# Microcontroller.net
KiCad netlist of a schematic drawn in Altium Designer
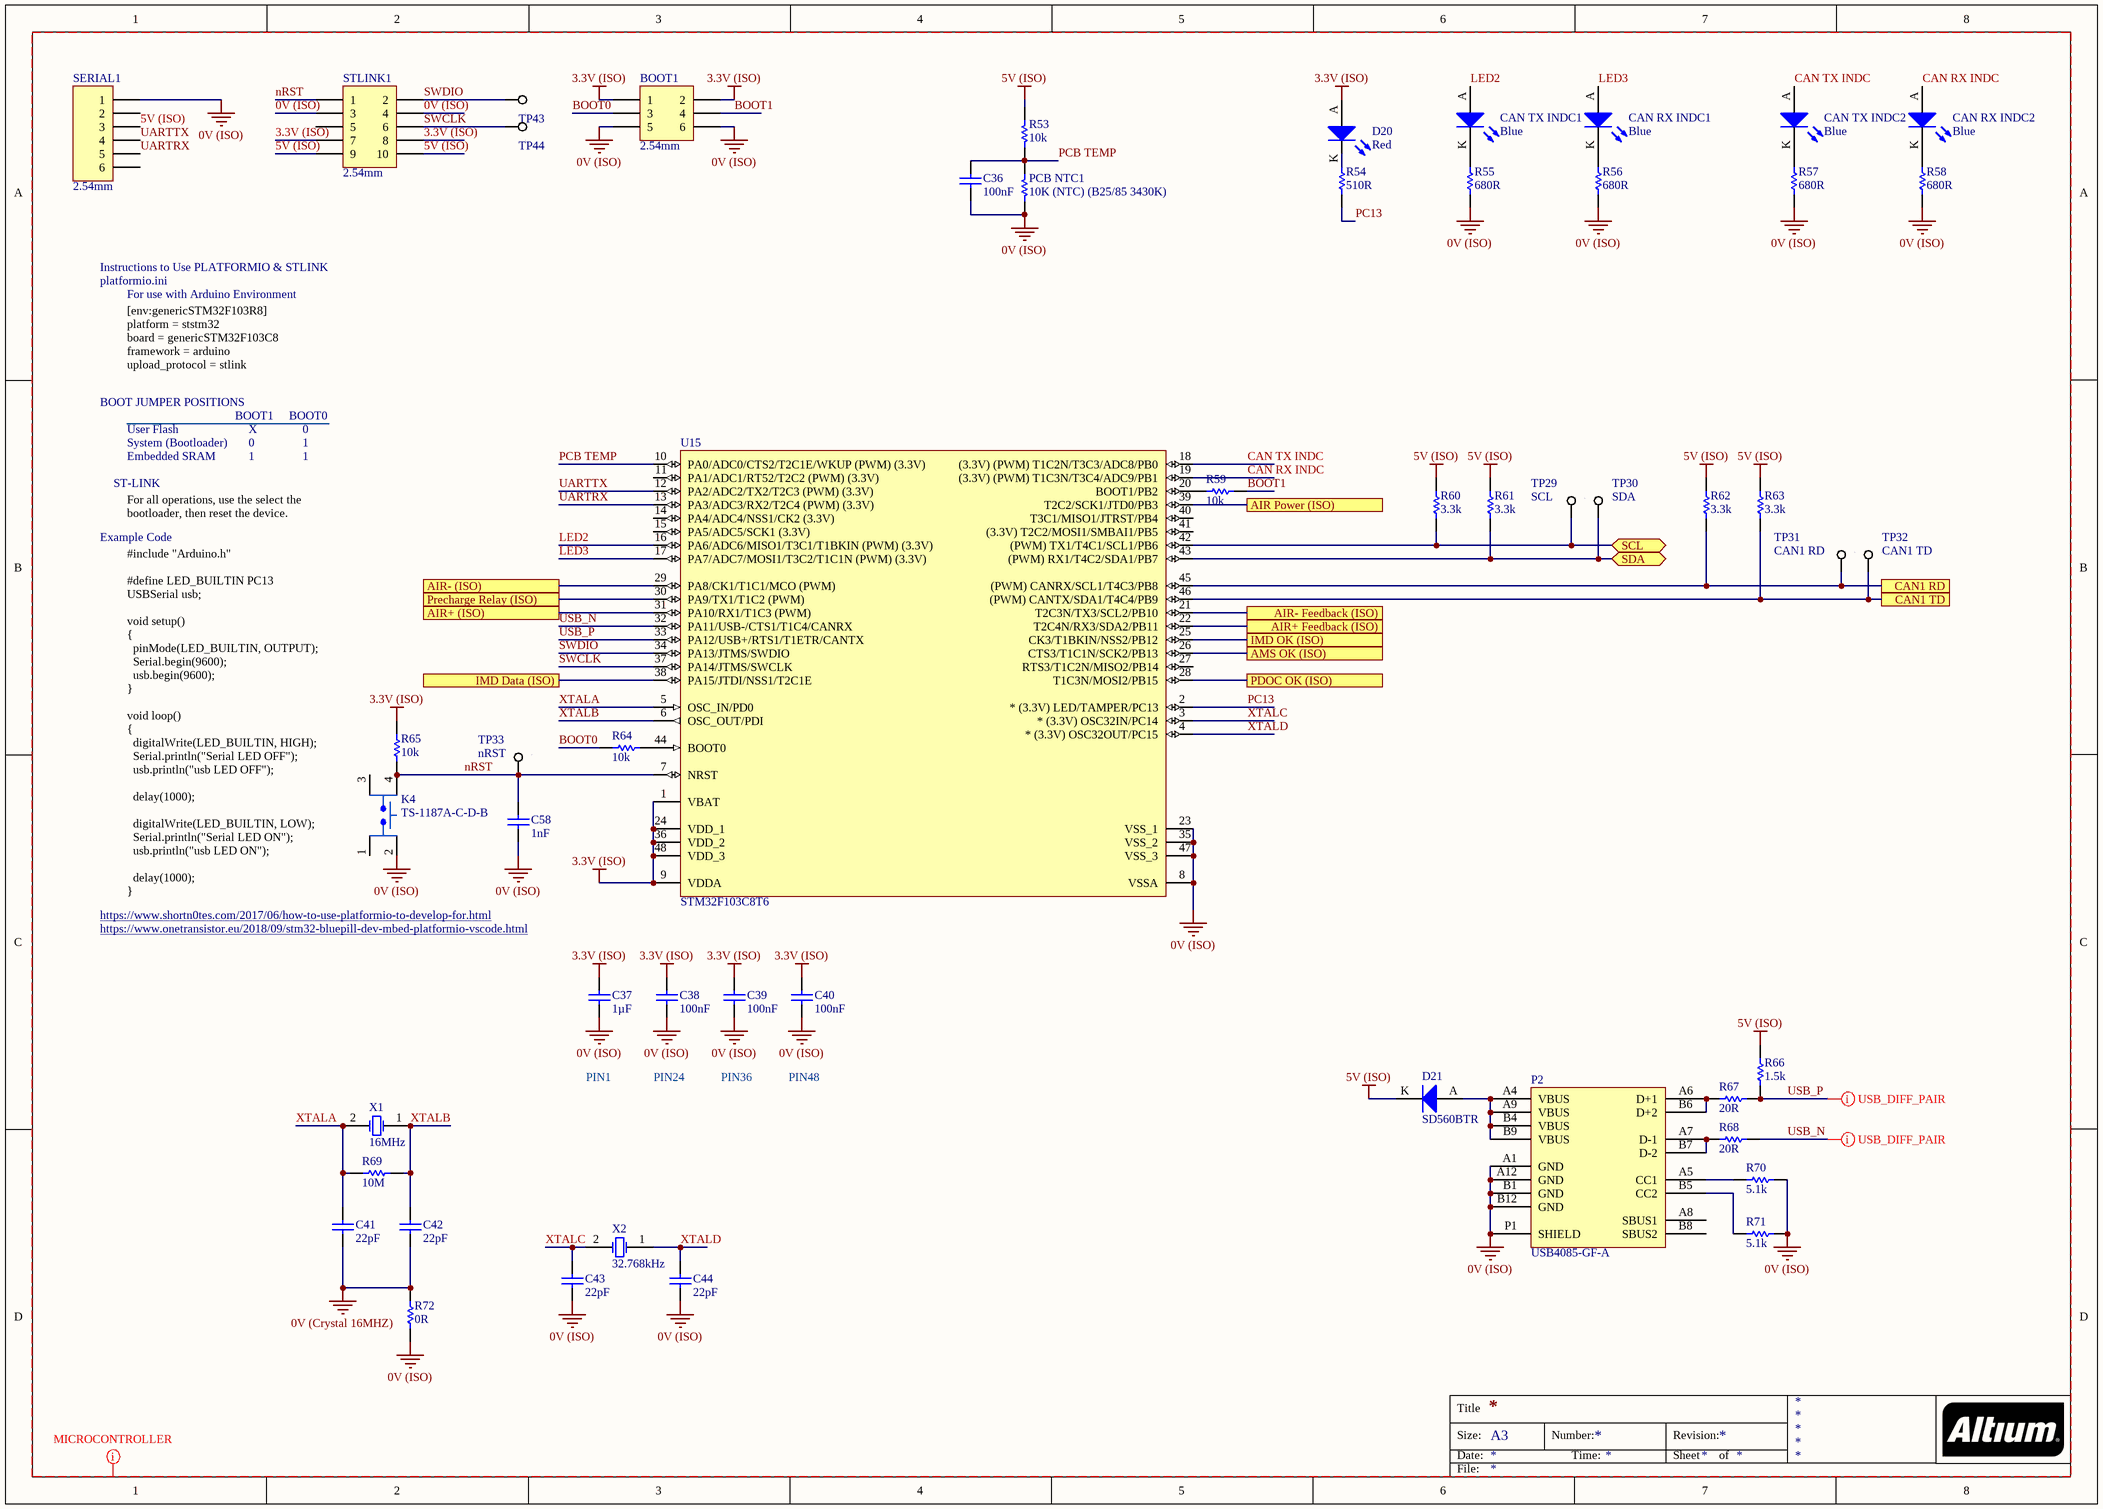
[diagram p0: Microcontroller.SchDoc]

(export (version "E")
  (design (tool "Eeschema 10.0.6"))
  (components
    (comp (ref "BOOT1")
      (value "2.54mm")
      (footprint "TH 2.54mm Header 2x3")
      (fields (field (name "PART NUMBER") "TH 2.54mm Header 2x3") (field (name "CONTACT") "NA"))
      (libsource (lib "ts_20-standard-connectors") (part "Header 2x3"))
    )
    (comp (ref "C36")
      (value "100nF")
      (footprint "0805")
      (fields
        (field (name "PART NUMBER") "GCM21BR71E104KA37L")
        (field (name "TOLERANCE") "10%")
        (field (name "MANUFACTURER") "muRata")
      )
      (libsource (lib "ts_20-standard-library") (part "Capacitor"))
    )
    (comp (ref "C37")
      (value "1µF")
      (footprint "0805")
      (fields
        (field (name "PART NUMBER") "GCM21BR71H105KA03L")
        (field (name "TOLERANCE") "±10%")
        (field (name "MANUFACTURER") "muRata")
      )
      (libsource (lib "ts_20-standard-library") (part "Capacitor"))
    )
    (comp (ref "C38")
      (value "100nF")
      (footprint "0805")
      (fields
        (field (name "PART NUMBER") "GCM21BR71H104KA37L")
        (field (name "TOLERANCE") "±10%")
        (field (name "MANUFACTURER") "muRata")
      )
      (libsource (lib "ts_20-standard-library") (part "Capacitor"))
    )
    (comp (ref "C39")
      (value "100nF")
      (footprint "0805")
      (fields
        (field (name "PART NUMBER") "GCM21BR71H104KA37L")
        (field (name "TOLERANCE") "±10%")
        (field (name "MANUFACTURER") "muRata")
      )
      (libsource (lib "ts_20-standard-library") (part "Capacitor"))
    )
    (comp (ref "C40")
      (value "100nF")
      (footprint "0805")
      (fields
        (field (name "PART NUMBER") "GCM21BR71H104KA37L")
        (field (name "TOLERANCE") "±10%")
        (field (name "MANUFACTURER") "muRata")
      )
      (libsource (lib "ts_20-standard-library") (part "Capacitor"))
    )
    (comp (ref "C41")
      (value "22pF")
      (footprint "0805")
      (fields
        (field (name "PART NUMBER") "GRM21A5C2E220JW01D")
        (field (name "TOLERANCE") "±5%")
        (field (name "MANUFACTURER") "muRata")
      )
      (libsource (lib "ts_20-standard-library") (part "Capacitor"))
    )
    (comp (ref "C42")
      (value "22pF")
      (footprint "0805")
      (fields
        (field (name "PART NUMBER") "GRM21A5C2E220JW01D")
        (field (name "TOLERANCE") "±5%")
        (field (name "MANUFACTURER") "muRata")
      )
      (libsource (lib "ts_20-standard-library") (part "Capacitor"))
    )
    (comp (ref "C43")
      (value "22pF")
      (footprint "0805")
      (fields
        (field (name "PART NUMBER") "GRM21A5C2E220JW01D")
        (field (name "TOLERANCE") "±5%")
        (field (name "MANUFACTURER") "muRata")
      )
      (libsource (lib "ts_20-standard-library") (part "Capacitor"))
    )
    (comp (ref "C44")
      (value "22pF")
      (footprint "0805")
      (fields
        (field (name "PART NUMBER") "GRM21A5C2E220JW01D")
        (field (name "TOLERANCE") "±5%")
        (field (name "MANUFACTURER") "muRata")
      )
      (libsource (lib "ts_20-standard-library") (part "Capacitor"))
    )
    (comp (ref "C58")
      (value "1nF")
      (footprint "0805")
      (fields
        (field (name "PART NUMBER") "GCM21BR71H102KA37L")
        (field (name "TOLERANCE") "10%")
        (field (name "MANUFACTURER") "muRata")
      )
      (libsource (lib "ts_20-standard-library") (part "Capacitor"))
    )
    (comp (ref "CAN RX INDC1")
      (value "Blue")
      (footprint "0805 LED")
      (description "LED BLUE CLEAR 2012 SMD")
      (fields
        (field (name "PART NUMBER") "SML-MN2BCTT86C")
        (field (name "MANUFACTURER") "ROHM Semiconductor")
      )
      (libsource (lib "ts_20-standard-library") (part "LED"))
    )
    (comp (ref "CAN RX INDC2")
      (value "Blue")
      (footprint "0805 LED")
      (description "LED BLUE CLEAR 2012 SMD")
      (fields
        (field (name "PART NUMBER") "SML-MN2BCTT86C")
        (field (name "MANUFACTURER") "ROHM Semiconductor")
      )
      (libsource (lib "ts_20-standard-library") (part "LED"))
    )
    (comp (ref "CAN TX INDC1")
      (value "Blue")
      (footprint "0805 LED")
      (description "LED BLUE CLEAR 2012 SMD")
      (fields
        (field (name "PART NUMBER") "SML-MN2BCTT86C")
        (field (name "MANUFACTURER") "ROHM Semiconductor")
      )
      (libsource (lib "ts_20-standard-library") (part "LED"))
    )
    (comp (ref "CAN TX INDC2")
      (value "Blue")
      (footprint "0805 LED")
      (description "LED BLUE CLEAR 2012 SMD")
      (fields
        (field (name "PART NUMBER") "SML-MN2BCTT86C")
        (field (name "MANUFACTURER") "ROHM Semiconductor")
      )
      (libsource (lib "ts_20-standard-library") (part "LED"))
    )
    (comp (ref "D20")
      (value "Red")
      (footprint "0805 LED")
      (description "Red LED Indication - Discrete 1.75V 0805 (2012 Metric)")
      (fields (field (name "MANUFACTURER") "ROHM Semiconductor") (field (name "PART NUMBER") "SML-210LTT86"))
      (libsource (lib "ts_20-standard-library") (part "LED"))
    )
    (comp (ref "D21")
      (value "SD560BTR")
      (footprint "SMB Diode")
      (description "1.2V_F 600V 5A SMB")
      (fields
        (field (name "MANUFACTURER") "SMC Diode Solutions")
        (field (name "DIGIKEY PART NUMBER") "1655-1530-2-ND")
      )
      (libsource (lib "ts_20-standard-library") (part "Diode"))
    )
    (comp (ref "K4")
      (value "TS-1187A-C-D-B")
      (footprint "XKB SW-4.5")
      (description "TACTILE SWITCHES SPST 5.10MM X 5.10MM 0.80MM SMD ROHS")
      (fields (field (name "MANUFACTURER") "XKB Enerprise"))
      (libsource (lib "ts_20-standard-library") (part "SPST (Mom) Push Button"))
    )
    (comp (ref "P2")
      (value "USB4085-GF-A")
      (footprint "USB4085-GF-A")
      (description "USB - C (Type - C) USB 2.0 Receptacle Connector 16 Position Through Hole, Right Angle")
      (fields (field (name "DIGIKEY PART NUMBER") "2073-USB4085-GF-ACT-ND"))
      (libsource (lib "ts_20-standard-connectors") (part "USB4085-GF-A"))
    )
    (comp (ref "PCB NTC1")
      (value "10K (NTC) (B25/85 3430K)")
      (footprint "0805")
      (fields
        (field (name "PART NUMBER") "NTCS0805E3103FLT")
        (field (name "MANUFACTURER") "Vishay Beyschlag")
        (field (name "TOLERANCE") "0.01")
      )
      (libsource (lib "ts_20-standard-library") (part "Resistor"))
    )
    (comp (ref "R53")
      (value "10k")
      (footprint "0805")
      (fields
        (field (name "PART NUMBER") "RC0805FR0710KL")
        (field (name "MANUFACTURER") "YAGEO")
        (field (name "TOLERANCE") "0.01")
      )
      (libsource (lib "ts_20-standard-library") (part "Resistor"))
    )
    (comp (ref "R54")
      (value "510R")
      (footprint "0805")
      (fields
        (field (name "MANUFACTURER") "YAGEO")
        (field (name "PART NUMBER") "RC0805FR07510RL")
        (field (name "TOLERANCE") "0.01")
      )
      (libsource (lib "ts_20-standard-library") (part "Resistor"))
    )
    (comp (ref "R55")
      (value "680R")
      (footprint "0805")
      (fields
        (field (name "PART NUMBER") "RC0805FR07680RL")
        (field (name "MANUFACTURER") "YAGEO")
        (field (name "TOLERANCE") "0.01")
      )
      (libsource (lib "ts_20-standard-library") (part "Resistor"))
    )
    (comp (ref "R56")
      (value "680R")
      (footprint "0805")
      (fields
        (field (name "PART NUMBER") "RC0805FR07680RL")
        (field (name "MANUFACTURER") "YAGEO")
        (field (name "TOLERANCE") "0.01")
      )
      (libsource (lib "ts_20-standard-library") (part "Resistor"))
    )
    (comp (ref "R57")
      (value "680R")
      (footprint "0805")
      (fields
        (field (name "PART NUMBER") "RC0805FR07680RL")
        (field (name "MANUFACTURER") "YAGEO")
        (field (name "TOLERANCE") "0.01")
      )
      (libsource (lib "ts_20-standard-library") (part "Resistor"))
    )
    (comp (ref "R58")
      (value "680R")
      (footprint "0805")
      (fields
        (field (name "PART NUMBER") "RC0805FR07680RL")
        (field (name "MANUFACTURER") "YAGEO")
        (field (name "TOLERANCE") "0.01")
      )
      (libsource (lib "ts_20-standard-library") (part "Resistor"))
    )
    (comp (ref "R59")
      (value "10k")
      (footprint "0805")
      (fields
        (field (name "PART NUMBER") "RC0805FR0710KL")
        (field (name "MANUFACTURER") "YAGEO")
        (field (name "TOLERANCE") "0.01")
      )
      (libsource (lib "ts_20-standard-library") (part "Resistor"))
    )
    (comp (ref "R60")
      (value "3.3k")
      (footprint "0805")
      (fields
        (field (name "PART NUMBER") "RC0805FR073K3L")
        (field (name "MANUFACTURER") "YAGEO")
        (field (name "TOLERANCE") "0.01")
      )
      (libsource (lib "ts_20-standard-library") (part "Resistor"))
    )
    (comp (ref "R61")
      (value "3.3k")
      (footprint "0805")
      (fields
        (field (name "PART NUMBER") "RC0805FR073K3L")
        (field (name "MANUFACTURER") "YAGEO")
        (field (name "TOLERANCE") "0.01")
      )
      (libsource (lib "ts_20-standard-library") (part "Resistor"))
    )
    (comp (ref "R62")
      (value "3.3k")
      (footprint "0805")
      (fields
        (field (name "PART NUMBER") "RC0805FR073K3L")
        (field (name "MANUFACTURER") "YAGEO")
        (field (name "TOLERANCE") "0.01")
      )
      (libsource (lib "ts_20-standard-library") (part "Resistor"))
    )
    (comp (ref "R63")
      (value "3.3k")
      (footprint "0805")
      (fields
        (field (name "PART NUMBER") "RC0805FR073K3L")
        (field (name "MANUFACTURER") "YAGEO")
        (field (name "TOLERANCE") "0.01")
      )
      (libsource (lib "ts_20-standard-library") (part "Resistor"))
    )
    (comp (ref "R64")
      (value "10k")
      (footprint "0805")
      (fields
        (field (name "PART NUMBER") "RC0805FR0710KL")
        (field (name "MANUFACTURER") "YAGEO")
        (field (name "TOLERANCE") "0.01")
      )
      (libsource (lib "ts_20-standard-library") (part "Resistor"))
    )
    (comp (ref "R65")
      (value "10k")
      (footprint "0805")
      (fields
        (field (name "MANUFACTURER") "YAGEO")
        (field (name "PART NUMBER") "RC0805FR0710KL")
        (field (name "TOLERANCE") "0.01")
      )
      (libsource (lib "ts_20-standard-library") (part "Resistor"))
    )
    (comp (ref "R66")
      (value "1.5k")
      (footprint "0805")
      (fields
        (field (name "PART NUMBER") "RC0805FR071K5L")
        (field (name "MANUFACTURER") "YAGEO")
        (field (name "TOLERANCE") "0.01")
      )
      (libsource (lib "ts_20-standard-library") (part "Resistor"))
    )
    (comp (ref "R67")
      (value "20R")
      (footprint "0805")
      (fields
        (field (name "PART NUMBER") "RC0805FR0720RL")
        (field (name "MANUFACTURER") "YAGEO")
        (field (name "TOLERANCE") "0.01")
      )
      (libsource (lib "ts_20-standard-library") (part "Resistor"))
    )
    (comp (ref "R68")
      (value "20R")
      (footprint "0805")
      (fields
        (field (name "PART NUMBER") "RC0805FR0720RL")
        (field (name "MANUFACTURER") "YAGEO")
        (field (name "TOLERANCE") "0.01")
      )
      (libsource (lib "ts_20-standard-library") (part "Resistor"))
    )
    (comp (ref "R69")
      (value "10M")
      (footprint "0805")
      (fields
        (field (name "PART NUMBER") "RC0805FR0710ML")
        (field (name "MANUFACTURER") "YAGEO")
        (field (name "TOLERANCE") "0.01")
      )
      (libsource (lib "ts_20-standard-library") (part "Resistor"))
    )
    (comp (ref "R70")
      (value "5.1k")
      (footprint "0805")
      (fields
        (field (name "PART NUMBER") "RC0805FR075K1L")
        (field (name "MANUFACTURER") "YAGEO")
        (field (name "TOLERANCE") "0.01")
      )
      (libsource (lib "ts_20-standard-library") (part "Resistor"))
    )
    (comp (ref "R71")
      (value "5.1k")
      (footprint "0805")
      (fields
        (field (name "PART NUMBER") "RC0805FR075K1L")
        (field (name "MANUFACTURER") "YAGEO")
        (field (name "TOLERANCE") "0.01")
      )
      (libsource (lib "ts_20-standard-library") (part "Resistor"))
    )
    (comp (ref "R72")
      (value "0R")
      (footprint "0805")
      (fields
        (field (name "PART NUMBER") "RC0805FR070RL")
        (field (name "MANUFACTURER") "YAGEO")
        (field (name "TOLERANCE") "0.01")
      )
      (libsource (lib "ts_20-standard-library") (part "Resistor"))
    )
    (comp (ref "SERIAL1")
      (value "2.54mm")
      (footprint "TH 2.54mm Header 1x6")
      (fields (field (name "PART NUMBER") "TH 2.54mm Header 1x6") (field (name "CONTACT") "NA"))
      (libsource (lib "ts_20-standard-connectors") (part "Header 1x6"))
    )
    (comp (ref "STLINK1")
      (value "2.54mm")
      (footprint "TH 2.54mm Header 2x5")
      (fields (field (name "PART NUMBER") "TH 2.54mm Header 2x5") (field (name "CONTACT") "NA"))
      (libsource (lib "ts_20-standard-connectors") (part "Header 2x5"))
    )
    (comp (ref "TP29")
      (value "SCL")
      (footprint "SMD Test Point 1mm")
      (fields (field (name "PART NUMBER") "SMD Test Point Small") (field (name "CONTACT") "NA"))
      (libsource (lib "ts_20-standard-connectors") (part "Test Point Small"))
    )
    (comp (ref "TP30")
      (value "SDA")
      (footprint "SMD Test Point 1mm")
      (fields (field (name "PART NUMBER") "SMD Test Point Small") (field (name "CONTACT") "NA"))
      (libsource (lib "ts_20-standard-connectors") (part "Test Point Small"))
    )
    (comp (ref "TP31")
      (value "CAN1 RD")
      (footprint "SMD Test Point 1mm")
      (fields (field (name "PART NUMBER") "SMD Test Point Small") (field (name "CONTACT") "NA"))
      (libsource (lib "ts_20-standard-connectors") (part "Test Point Small"))
    )
    (comp (ref "TP32")
      (value "CAN1 TD")
      (footprint "SMD Test Point 1mm")
      (fields (field (name "PART NUMBER") "SMD Test Point Small") (field (name "CONTACT") "NA"))
      (libsource (lib "ts_20-standard-connectors") (part "Test Point Small"))
    )
    (comp (ref "TP33")
      (value "nRST")
      (footprint "SMD Test Point 1mm")
      (fields (field (name "PART NUMBER") "SMD Test Point Small") (field (name "CONTACT") "NA"))
      (libsource (lib "ts_20-standard-connectors") (part "Test Point Small"))
    )
    (comp (ref "TP43")
      (value "0mm")
      (footprint "SMD Test Point 1mm")
      (fields (field (name "PART NUMBER") "SMD Test Point Small") (field (name "CONTACT") "NA"))
      (libsource (lib "ts_20-standard-connectors") (part "Test Point Small"))
    )
    (comp (ref "TP44")
      (value "0mm")
      (footprint "SMD Test Point 1mm")
      (fields (field (name "PART NUMBER") "SMD Test Point Small") (field (name "CONTACT") "NA"))
      (libsource (lib "ts_20-standard-connectors") (part "Test Point Small"))
    )
    (comp (ref "U15")
      (value "STM32F103C8T6")
      (footprint "STM 48-LQFP")
      (description "ARM® Cortex®-M3 STM32F1 Microcontroller IC 32-Bit 72MHz 64KB (64K x 8) FLASH")
      (fields
        (field (name "MANUFACTURER") "STMicroelectronics")
        (field (name "DIGIKEY PART NUMBER") "497-6063-ND")
      )
      (libsource (lib "ts_20-standard-library") (part "STM32F103C8T6"))
    )
    (comp (ref "X1")
      (value "16MHz")
      (footprint "Abracon HC-49/US")
      (fields
        (field (name "PART NUMBER") "ABLS-16.000MHZ-B4-T")
        (field (name "MANUFACTURER") "Abracon LLC")
        (field (name "DIGIKEY PART NUMBER") "535-10226-1-ND")
      )
      (libsource (lib "ts_20-standard-library") (part "Crystal"))
    )
    (comp (ref "X2")
      (value "32.768kHz")
      (footprint "EPSON 2-SMD")
      (fields
        (field (name "PART NUMBER") "FC-135 32.7680KA-A5")
        (field (name "MANUFACTURER") "EPSON")
        (field (name "DIGIKEY PART NUMBER") "SER4103TR-ND")
      )
      (libsource (lib "ts_20-standard-library") (part "Crystal"))
    )
  )
  (nets
    (net (code "1") (name "/AIR Power (ISO)") (class "Default")
      (node (ref "U15") (pin "39") (pinfunction "T2C2/SCK1/JTD0/PB3_39") (pintype "bidirectional"))
    )
    (net (code "2") (name "/AIR+ (ISO)") (class "Default")
      (node (ref "U15") (pin "31") (pinfunction "PA10/RX1/T1C3_(PWM)_31") (pintype "bidirectional"))
    )
    (net (code "3") (name "/AIR+ Feedback (ISO)") (class "Default")
      (node (ref "U15") (pin "22") (pinfunction "T2C4N/RX3/SDA2/PB11_22") (pintype "bidirectional"))
    )
    (net (code "4") (name "/AIR- (ISO)") (class "Default")
      (node (ref "U15") (pin "29") (pinfunction "PA8/CK1/T1C1/MCO_(PWM)_29") (pintype "bidirectional"))
    )
    (net (code "5") (name "/AIR- Feedback (ISO)") (class "Default")
      (node (ref "U15") (pin "21") (pinfunction "T2C3N/TX3/SCL2/PB10_21") (pintype "bidirectional"))
    )
    (net (code "6") (name "/AMS OK (ISO)") (class "Default")
      (node (ref "U15") (pin "26") (pinfunction "CTS3/T1C1N/SCK2/PB13_26") (pintype "bidirectional"))
    )
    (net (code "7") (name "/BOOT0") (class "Default")
      (node (ref "BOOT1") (pin "3") (pinfunction "3_3") (pintype "passive"))
      (node (ref "R64") (pin "1") (pinfunction "1_1") (pintype "passive"))
    )
    (net (code "8") (name "/BOOT1") (class "Default")
      (node (ref "BOOT1") (pin "4") (pinfunction "4_4") (pintype "passive"))
      (node (ref "R59") (pin "2") (pinfunction "2_2") (pintype "passive"))
    )
    (net (code "9") (name "/CAN RX INDC") (class "Default")
      (node (ref "CAN RX INDC2") (pin "A") (pinfunction "A_A") (pintype "passive"))
      (node (ref "U15") (pin "19") (pinfunction "(3.3V)_(PWM)_T1C3N/T3C4/ADC9/PB1_19") (pintype "bidirectional"))
    )
    (net (code "10") (name "/CAN TX INDC") (class "Default")
      (node (ref "CAN TX INDC2") (pin "A") (pinfunction "A_A") (pintype "passive"))
      (node (ref "U15") (pin "18") (pinfunction "(3.3V)_(PWM)_T1C2N/T3C3/ADC8/PB0_18") (pintype "bidirectional"))
    )
    (net (code "11") (name "/CAN1 RD") (class "Default")
      (node (ref "R62") (pin "1") (pinfunction "1_1") (pintype "passive"))
      (node (ref "TP31") (pin "1") (pinfunction "1_1") (pintype "passive"))
      (node (ref "U15") (pin "45") (pinfunction "(PWM)_CANRX/SCL1/T4C3/PB8_45") (pintype "bidirectional"))
    )
    (net (code "12") (name "/CAN1 TD") (class "Default")
      (node (ref "R63") (pin "1") (pinfunction "1_1") (pintype "passive"))
      (node (ref "TP32") (pin "1") (pinfunction "1_1") (pintype "passive"))
      (node (ref "U15") (pin "46") (pinfunction "(PWM)_CANTX/SDA1/T4C4/PB9_46") (pintype "bidirectional"))
    )
    (net (code "13") (name "/IMD Data (ISO)") (class "Default")
      (node (ref "U15") (pin "38") (pinfunction "PA15/JTDI/NSS1/T2C1E_38") (pintype "bidirectional"))
    )
    (net (code "14") (name "/IMD OK (ISO)") (class "Default")
      (node (ref "U15") (pin "25") (pinfunction "CK3/T1BKIN/NSS2/PB12_25") (pintype "bidirectional"))
    )
    (net (code "15") (name "/LED2") (class "Default")
      (node (ref "CAN TX INDC1") (pin "A") (pinfunction "A_A") (pintype "passive"))
      (node (ref "U15") (pin "16") (pinfunction "PA6/ADC6/MISO1/T3C1/T1BKIN_(PWM)_(3.3V)_16") (pintype "bidirectional"))
    )
    (net (code "16") (name "/LED3") (class "Default")
      (node (ref "CAN RX INDC1") (pin "A") (pinfunction "A_A") (pintype "passive"))
      (node (ref "U15") (pin "17") (pinfunction "PA7/ADC7/MOSI1/T3C2/T1C1N_(PWM)_(3.3V)_17") (pintype "bidirectional"))
    )
    (net (code "17") (name "/PC13") (class "Default")
      (node (ref "R54") (pin "1") (pinfunction "1_1") (pintype "passive"))
      (node (ref "U15") (pin "2") (pinfunction "*_(3.3V)_LED/TAMPER/PC13_2") (pintype "bidirectional"))
    )
    (net (code "18") (name "/PCB TEMP") (class "Default")
      (node (ref "C36") (pin "2") (pinfunction "2_2") (pintype "passive"))
      (node (ref "PCB NTC1") (pin "2") (pinfunction "2_2") (pintype "passive"))
      (node (ref "R53") (pin "1") (pinfunction "1_1") (pintype "passive"))
      (node (ref "U15") (pin "10") (pinfunction "PA0/ADC0/CTS2/T2C1E/WKUP_(PWM)_(3.3V)_10") (pintype "bidirectional"))
    )
    (net (code "19") (name "/PDOC OK (ISO)") (class "Default")
      (node (ref "U15") (pin "28") (pinfunction "T1C3N/MOSI2/PB15_28") (pintype "bidirectional"))
    )
    (net (code "20") (name "/Precharge Relay (ISO)") (class "Default")
      (node (ref "U15") (pin "30") (pinfunction "PA9/TX1/T1C2_(PWM)_30") (pintype "bidirectional"))
    )
    (net (code "21") (name "/SCL") (class "Default")
      (node (ref "R60") (pin "1") (pinfunction "1_1") (pintype "passive"))
      (node (ref "TP29") (pin "1") (pinfunction "1_1") (pintype "passive"))
      (node (ref "U15") (pin "42") (pinfunction "(PWM)_TX1/T4C1/SCL1/PB6_42") (pintype "bidirectional"))
    )
    (net (code "22") (name "/SDA") (class "Default")
      (node (ref "R61") (pin "1") (pinfunction "1_1") (pintype "passive"))
      (node (ref "TP30") (pin "1") (pinfunction "1_1") (pintype "passive"))
      (node (ref "U15") (pin "43") (pinfunction "(PWM)_RX1/T4C2/SDA1/PB7_43") (pintype "bidirectional"))
    )
    (net (code "23") (name "/SWCLK") (class "Default")
      (node (ref "STLINK1") (pin "6") (pinfunction "6_6") (pintype "passive"))
      (node (ref "TP44") (pin "1") (pinfunction "1_1") (pintype "passive"))
      (node (ref "U15") (pin "37") (pinfunction "PA14/JTMS/SWCLK_37") (pintype "bidirectional"))
    )
    (net (code "24") (name "/SWDIO") (class "Default")
      (node (ref "STLINK1") (pin "2") (pinfunction "2_2") (pintype "passive"))
      (node (ref "TP43") (pin "1") (pinfunction "1_1") (pintype "passive"))
      (node (ref "U15") (pin "34") (pinfunction "PA13/JTMS/SWDIO_34") (pintype "bidirectional"))
    )
    (net (code "25") (name "/UARTRX") (class "Default")
      (node (ref "SERIAL1") (pin "5") (pinfunction "5_5") (pintype "passive"))
      (node (ref "U15") (pin "13") (pinfunction "PA3/ADC3/RX2/T2C4_(PWM)_(3.3V)_13") (pintype "bidirectional"))
    )
    (net (code "26") (name "/UARTTX") (class "Default")
      (node (ref "SERIAL1") (pin "4") (pinfunction "4_4") (pintype "passive"))
      (node (ref "U15") (pin "12") (pinfunction "PA2/ADC2/TX2/T2C3_(PWM)_(3.3V)_12") (pintype "bidirectional"))
    )
    (net (code "27") (name "/USB_N") (class "Default")
      (node (ref "R68") (pin "2") (pinfunction "2_2") (pintype "passive"))
      (node (ref "U15") (pin "32") (pinfunction "PA11/USB-/CTS1/T1C4/CANRX_32") (pintype "bidirectional"))
    )
    (net (code "28") (name "/USB_P") (class "Default")
      (node (ref "R66") (pin "1") (pinfunction "1_1") (pintype "passive"))
      (node (ref "R67") (pin "2") (pinfunction "2_2") (pintype "passive"))
      (node (ref "U15") (pin "33") (pinfunction "PA12/USB+/RTS1/T1ETR/CANTX_33") (pintype "bidirectional"))
    )
    (net (code "29") (name "/XTALA") (class "Default")
      (node (ref "C41") (pin "2") (pinfunction "2_2") (pintype "passive"))
      (node (ref "R69") (pin "2") (pinfunction "2_2") (pintype "passive"))
      (node (ref "U15") (pin "5") (pinfunction "OSC_IN/PD0_5") (pintype "input"))
      (node (ref "X1") (pin "2") (pinfunction "OSC2_2") (pintype "passive"))
    )
    (net (code "30") (name "/XTALB") (class "Default")
      (node (ref "C42") (pin "2") (pinfunction "2_2") (pintype "passive"))
      (node (ref "R69") (pin "1") (pinfunction "1_1") (pintype "passive"))
      (node (ref "U15") (pin "6") (pinfunction "OSC_OUT/PDI_6") (pintype "output"))
      (node (ref "X1") (pin "1") (pinfunction "OSC1_1") (pintype "passive"))
    )
    (net (code "31") (name "/XTALC") (class "Default")
      (node (ref "C43") (pin "2") (pinfunction "2_2") (pintype "passive"))
      (node (ref "U15") (pin "3") (pinfunction "*_(3.3V)_OSC32IN/PC14_3") (pintype "bidirectional"))
      (node (ref "X2") (pin "2") (pinfunction "OSC2_2") (pintype "passive"))
    )
    (net (code "32") (name "/XTALD") (class "Default")
      (node (ref "C44") (pin "2") (pinfunction "2_2") (pintype "passive"))
      (node (ref "U15") (pin "4") (pinfunction "*_(3.3V)_OSC32OUT/PC15_4") (pintype "bidirectional"))
      (node (ref "X2") (pin "1") (pinfunction "OSC1_1") (pintype "passive"))
    )
    (net (code "33") (name "/nRST") (class "Default")
      (node (ref "C58") (pin "2") (pinfunction "2_2") (pintype "passive"))
      (node (ref "K4") (pin "4") (pinfunction "VDD_4") (pintype "passive"))
      (node (ref "R65") (pin "1") (pinfunction "1_1") (pintype "passive"))
      (node (ref "STLINK1") (pin "1") (pinfunction "1_1") (pintype "passive"))
      (node (ref "TP33") (pin "1") (pinfunction "1_1") (pintype "passive"))
      (node (ref "U15") (pin "7") (pinfunction "NRST_7") (pintype "bidirectional"))
    )
    (net (code "34") (name "0V (Crystal 16MHZ)") (class "Default")
      (node (ref "C41") (pin "1") (pinfunction "1_1") (pintype "passive"))
      (node (ref "C42") (pin "1") (pinfunction "1_1") (pintype "passive"))
      (node (ref "R72") (pin "2") (pinfunction "2_2") (pintype "passive"))
    )
    (net (code "35") (name "0V (ISO)") (class "Default")
      (node (ref "BOOT1") (pin "5") (pinfunction "5_5") (pintype "passive"))
      (node (ref "BOOT1") (pin "6") (pinfunction "6_6") (pintype "passive"))
      (node (ref "C36") (pin "1") (pinfunction "1_1") (pintype "passive"))
      (node (ref "C37") (pin "1") (pinfunction "1_1") (pintype "passive"))
      (node (ref "C38") (pin "1") (pinfunction "1_1") (pintype "passive"))
      (node (ref "C39") (pin "1") (pinfunction "1_1") (pintype "passive"))
      (node (ref "C40") (pin "1") (pinfunction "1_1") (pintype "passive"))
      (node (ref "C43") (pin "1") (pinfunction "1_1") (pintype "passive"))
      (node (ref "C44") (pin "1") (pinfunction "1_1") (pintype "passive"))
      (node (ref "C58") (pin "1") (pinfunction "1_1") (pintype "passive"))
      (node (ref "K4") (pin "2") (pinfunction "VDD_2") (pintype "passive"))
      (node (ref "P2") (pin "A1") (pinfunction "GND_A1") (pintype "passive"))
      (node (ref "P2") (pin "A12") (pinfunction "GND_A12") (pintype "passive"))
      (node (ref "P2") (pin "B1") (pinfunction "GND_B1") (pintype "passive"))
      (node (ref "P2") (pin "B12") (pinfunction "GND_B12") (pintype "passive"))
      (node (ref "P2") (pin "P1") (pinfunction "SHIELD_P1") (pintype "passive"))
      (node (ref "PCB NTC1") (pin "1") (pinfunction "1_1") (pintype "passive"))
      (node (ref "R55") (pin "1") (pinfunction "1_1") (pintype "passive"))
      (node (ref "R56") (pin "1") (pinfunction "1_1") (pintype "passive"))
      (node (ref "R57") (pin "1") (pinfunction "1_1") (pintype "passive"))
      (node (ref "R58") (pin "1") (pinfunction "1_1") (pintype "passive"))
      (node (ref "R70") (pin "2") (pinfunction "2_2") (pintype "passive"))
      (node (ref "R71") (pin "2") (pinfunction "2_2") (pintype "passive"))
      (node (ref "R72") (pin "1") (pinfunction "1_1") (pintype "passive"))
      (node (ref "SERIAL1") (pin "1") (pinfunction "1_1") (pintype "passive"))
      (node (ref "STLINK1") (pin "3") (pinfunction "3_3") (pintype "passive"))
      (node (ref "STLINK1") (pin "4") (pinfunction "4_4") (pintype "passive"))
      (node (ref "U15") (pin "23") (pinfunction "VSS_1_23") (pintype "power_in"))
      (node (ref "U15") (pin "35") (pinfunction "VSS_2_35") (pintype "power_in"))
      (node (ref "U15") (pin "47") (pinfunction "VSS_3_47") (pintype "power_in"))
      (node (ref "U15") (pin "8") (pinfunction "VSSA_8") (pintype "power_in"))
    )
    (net (code "36") (name "3.3V (ISO)") (class "Default")
      (node (ref "BOOT1") (pin "1") (pinfunction "1_1") (pintype "passive"))
      (node (ref "BOOT1") (pin "2") (pinfunction "2_2") (pintype "passive"))
      (node (ref "C37") (pin "2") (pinfunction "2_2") (pintype "passive"))
      (node (ref "C38") (pin "2") (pinfunction "2_2") (pintype "passive"))
      (node (ref "C39") (pin "2") (pinfunction "2_2") (pintype "passive"))
      (node (ref "C40") (pin "2") (pinfunction "2_2") (pintype "passive"))
      (node (ref "D20") (pin "A") (pinfunction "A_A") (pintype "passive"))
      (node (ref "R65") (pin "2") (pinfunction "2_2") (pintype "passive"))
      (node (ref "STLINK1") (pin "7") (pinfunction "7_7") (pintype "passive"))
      (node (ref "STLINK1") (pin "8") (pinfunction "8_8") (pintype "passive"))
      (node (ref "U15") (pin "1") (pinfunction "VBAT_1") (pintype "power_in"))
      (node (ref "U15") (pin "24") (pinfunction "VDD_1_24") (pintype "power_in"))
      (node (ref "U15") (pin "36") (pinfunction "VDD_2_36") (pintype "power_in"))
      (node (ref "U15") (pin "48") (pinfunction "VDD_3_48") (pintype "power_in"))
      (node (ref "U15") (pin "9") (pinfunction "VDDA_9") (pintype "power_in"))
    )
    (net (code "37") (name "5V (ISO)") (class "Default")
      (node (ref "D21") (pin "K") (pinfunction "K_K") (pintype "passive"))
      (node (ref "R53") (pin "2") (pinfunction "2_2") (pintype "passive"))
      (node (ref "R60") (pin "2") (pinfunction "2_2") (pintype "passive"))
      (node (ref "R61") (pin "2") (pinfunction "2_2") (pintype "passive"))
      (node (ref "R62") (pin "2") (pinfunction "2_2") (pintype "passive"))
      (node (ref "R63") (pin "2") (pinfunction "2_2") (pintype "passive"))
      (node (ref "R66") (pin "2") (pinfunction "2_2") (pintype "passive"))
      (node (ref "SERIAL1") (pin "3") (pinfunction "3_3") (pintype "passive"))
      (node (ref "STLINK1") (pin "10") (pinfunction "10_10") (pintype "passive"))
      (node (ref "STLINK1") (pin "9") (pinfunction "9_9") (pintype "passive"))
    )
    (net (code "38") (name "Net-(CAN RX INDC1-PadK)") (class "Default")
      (node (ref "CAN RX INDC1") (pin "K") (pinfunction "K_K") (pintype "passive"))
      (node (ref "R56") (pin "2") (pinfunction "2_2") (pintype "passive"))
    )
    (net (code "39") (name "Net-(CAN RX INDC2-PadK)") (class "Default")
      (node (ref "CAN RX INDC2") (pin "K") (pinfunction "K_K") (pintype "passive"))
      (node (ref "R58") (pin "2") (pinfunction "2_2") (pintype "passive"))
    )
    (net (code "40") (name "Net-(CAN TX INDC1-PadK)") (class "Default")
      (node (ref "CAN TX INDC1") (pin "K") (pinfunction "K_K") (pintype "passive"))
      (node (ref "R55") (pin "2") (pinfunction "2_2") (pintype "passive"))
    )
    (net (code "41") (name "Net-(CAN TX INDC2-PadK)") (class "Default")
      (node (ref "CAN TX INDC2") (pin "K") (pinfunction "K_K") (pintype "passive"))
      (node (ref "R57") (pin "2") (pinfunction "2_2") (pintype "passive"))
    )
    (net (code "42") (name "Net-(D20-PadK)") (class "Default")
      (node (ref "D20") (pin "K") (pinfunction "K_K") (pintype "passive"))
      (node (ref "R54") (pin "2") (pinfunction "2_2") (pintype "passive"))
    )
    (net (code "43") (name "Net-(D21-PadA)") (class "Default")
      (node (ref "D21") (pin "A") (pinfunction "A_A") (pintype "passive"))
      (node (ref "P2") (pin "A4") (pinfunction "VBUS_A4") (pintype "passive"))
      (node (ref "P2") (pin "A9") (pinfunction "VBUS_A9") (pintype "passive"))
      (node (ref "P2") (pin "B4") (pinfunction "VBUS_B4") (pintype "passive"))
      (node (ref "P2") (pin "B9") (pinfunction "VBUS_B9") (pintype "passive"))
    )
    (net (code "44") (name "Net-(P2-CC1)") (class "Default")
      (node (ref "P2") (pin "A5") (pinfunction "CC1_A5") (pintype "passive"))
      (node (ref "R70") (pin "1") (pinfunction "1_1") (pintype "passive"))
    )
    (net (code "45") (name "Net-(P2-CC2)") (class "Default")
      (node (ref "P2") (pin "B5") (pinfunction "CC2_B5") (pintype "passive"))
      (node (ref "R71") (pin "1") (pinfunction "1_1") (pintype "passive"))
    )
    (net (code "46") (name "Net-(P2-D+1)") (class "Default")
      (node (ref "P2") (pin "A6") (pinfunction "D+1_A6") (pintype "passive"))
      (node (ref "P2") (pin "B6") (pinfunction "D+2_B6") (pintype "passive"))
      (node (ref "R67") (pin "1") (pinfunction "1_1") (pintype "passive"))
    )
    (net (code "47") (name "Net-(P2-D-1)") (class "Default")
      (node (ref "P2") (pin "A7") (pinfunction "D-1_A7") (pintype "passive"))
      (node (ref "P2") (pin "B7") (pinfunction "D-2_B7") (pintype "passive"))
      (node (ref "R68") (pin "1") (pinfunction "1_1") (pintype "passive"))
    )
    (net (code "48") (name "Net-(U15-BOOT0)") (class "Default")
      (node (ref "R64") (pin "2") (pinfunction "2_2") (pintype "passive"))
      (node (ref "U15") (pin "44") (pinfunction "BOOT0_44") (pintype "input"))
    )
    (net (code "49") (name "Net-(U15-BOOT1{slash}PB2)") (class "Default")
      (node (ref "R59") (pin "1") (pinfunction "1_1") (pintype "passive"))
      (node (ref "U15") (pin "20") (pinfunction "BOOT1/PB2_20") (pintype "bidirectional"))
    )
    (net (code "50") (name "unconnected-(K4-VDD-Pad1)") (class "Default")
      (node (ref "K4") (pin "1") (pinfunction "VDD_1") (pintype "passive"))
    )
    (net (code "51") (name "unconnected-(K4-VDD-Pad3)") (class "Default")
      (node (ref "K4") (pin "3") (pinfunction "VDD_3") (pintype "passive"))
    )
    (net (code "52") (name "unconnected-(P2-SBUS1-PadA8)") (class "Default")
      (node (ref "P2") (pin "A8") (pinfunction "SBUS1_A8") (pintype "passive"))
    )
    (net (code "53") (name "unconnected-(P2-SBUS2-PadB8)") (class "Default")
      (node (ref "P2") (pin "B8") (pinfunction "SBUS2_B8") (pintype "passive"))
    )
    (net (code "54") (name "unconnected-(SERIAL1-Pad2)") (class "Default")
      (node (ref "SERIAL1") (pin "2") (pinfunction "2_2") (pintype "passive"))
    )
    (net (code "55") (name "unconnected-(SERIAL1-Pad6)") (class "Default")
      (node (ref "SERIAL1") (pin "6") (pinfunction "6_6") (pintype "passive"))
    )
    (net (code "56") (name "unconnected-(STLINK1-Pad5)") (class "Default")
      (node (ref "STLINK1") (pin "5") (pinfunction "5_5") (pintype "passive"))
    )
    (net (code "57") (name "unconnected-(U15-(3.3V)_T2C2{slash}MOSI1{slash}SMBAI1{slash}PB5-Pad41)") (class "Default")
      (node (ref "U15") (pin "41") (pinfunction "(3.3V)_T2C2/MOSI1/SMBAI1/PB5_41") (pintype "bidirectional"))
    )
    (net (code "58") (name "unconnected-(U15-PA1{slash}ADC1{slash}RT52{slash}T2C2_(PWM)_(3.3V)-Pad11)") (class "Default")
      (node (ref "U15") (pin "11") (pinfunction "PA1/ADC1/RT52/T2C2_(PWM)_(3.3V)_11") (pintype "bidirectional"))
    )
    (net (code "59") (name "unconnected-(U15-PA4{slash}ADC4{slash}NSS1{slash}CK2_(3.3V)-Pad14)") (class "Default")
      (node (ref "U15") (pin "14") (pinfunction "PA4/ADC4/NSS1/CK2_(3.3V)_14") (pintype "bidirectional"))
    )
    (net (code "60") (name "unconnected-(U15-PA5{slash}ADC5{slash}SCK1_(3.3V)-Pad15)") (class "Default")
      (node (ref "U15") (pin "15") (pinfunction "PA5/ADC5/SCK1_(3.3V)_15") (pintype "bidirectional"))
    )
    (net (code "61") (name "unconnected-(U15-RTS3{slash}T1C2N{slash}MISO2{slash}PB14-Pad27)") (class "Default")
      (node (ref "U15") (pin "27") (pinfunction "RTS3/T1C2N/MISO2/PB14_27") (pintype "bidirectional"))
    )
    (net (code "62") (name "unconnected-(U15-T3C1{slash}MISO1{slash}JTRST{slash}PB4-Pad40)") (class "Default")
      (node (ref "U15") (pin "40") (pinfunction "T3C1/MISO1/JTRST/PB4_40") (pintype "bidirectional"))
    )
  )
)
